# OsciladorLocal.net
KiCad netlist of a schematic drawn in Altium Designer
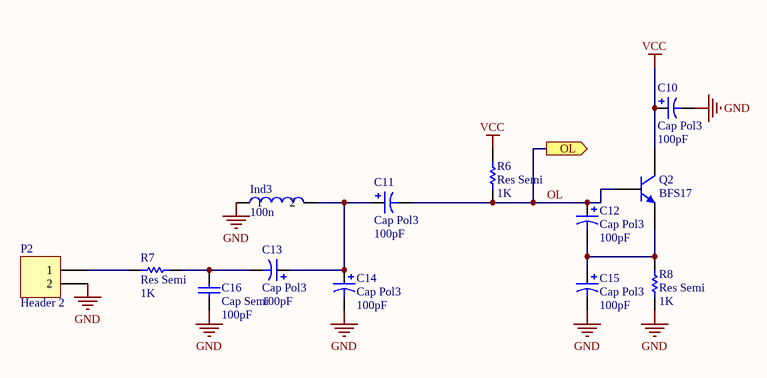
[diagram p0: OsciladorLocal.SchDoc]

(export (version "E")
  (design (tool "Eeschema 10.0.6"))
  (components
    (comp (ref "C10")
      (value "Cap Pol3")
      (footprint "C0805")
      (description "Polarized Capacitor (Surface Mount)")
      (fields (field (name "ALTIUM_VALUE") "100pF") (field (name "PUBLISHER") "Altium Limited"))
      (libsource (lib "Miscellaneous Devices") (part "Cap Pol3"))
    )
    (comp (ref "C11")
      (value "Cap Pol3")
      (footprint "C0805")
      (description "Polarized Capacitor (Surface Mount)")
      (fields (field (name "ALTIUM_VALUE") "100pF") (field (name "PUBLISHER") "Altium Limited"))
      (libsource (lib "Miscellaneous Devices") (part "Cap Pol3"))
    )
    (comp (ref "C12")
      (value "Cap Pol3")
      (footprint "C0805")
      (description "Polarized Capacitor (Surface Mount)")
      (fields (field (name "ALTIUM_VALUE") "100pF") (field (name "PUBLISHER") "Altium Limited"))
      (libsource (lib "Miscellaneous Devices") (part "Cap Pol3"))
    )
    (comp (ref "C13")
      (value "Cap Pol3")
      (footprint "C0805")
      (description "Polarized Capacitor (Surface Mount)")
      (fields (field (name "ALTIUM_VALUE") "100pF") (field (name "PUBLISHER") "Altium Limited"))
      (libsource (lib "Miscellaneous Devices") (part "Cap Pol3"))
    )
    (comp (ref "C14")
      (value "Cap Pol3")
      (footprint "C0805")
      (description "Polarized Capacitor (Surface Mount)")
      (fields (field (name "ALTIUM_VALUE") "100pF") (field (name "PUBLISHER") "Altium Limited"))
      (libsource (lib "Miscellaneous Devices") (part "Cap Pol3"))
    )
    (comp (ref "C15")
      (value "Cap Pol3")
      (footprint "C0805")
      (description "Polarized Capacitor (Surface Mount)")
      (fields (field (name "ALTIUM_VALUE") "100pF") (field (name "PUBLISHER") "Altium Limited"))
      (libsource (lib "Miscellaneous Devices") (part "Cap Pol3"))
    )
    (comp (ref "C16")
      (value "Cap Semi")
      (footprint "C1206")
      (description "Capacitor (Semiconductor SIM Model)")
      (fields (field (name "ALTIUM_VALUE") "100pF") (field (name "PUBLISHER") "Altium Limited"))
      (libsource (lib "Miscellaneous Devices") (part "Cap Semi"))
    )
    (comp (ref "Ind3")
      (value "Ind2")
      (footprint "Ind_3mm")
      (fields (field (name "VALOR") "100n"))
      (libsource (lib "epf") (part "Ind2"))
    )
    (comp (ref "P2")
      (value "Header 2")
      (footprint "HDR1X2")
      (description "Header, 2-Pin")
      (fields (field (name "PUBLISHER") "Altium Limited"))
      (libsource (lib "Miscellaneous Connectors") (part "Header 2"))
    )
    (comp (ref "Q2")
      (value "BFS17")
      (footprint "SOT23_N")
      (description "NPN 1 GHz Wideband Transistor")
      (fields (field (name "PUBLISHER") "Altium Limited"))
      (libsource (lib "Philips Discrete BJT - RF Transistor") (part "BFS17"))
    )
    (comp (ref "R6")
      (value "Res Semi")
      (footprint "2012[0805]")
      (description "Semiconductor Resistor")
      (fields (field (name "ALTIUM_VALUE") "1K") (field (name "PUBLISHER") "Altium Limited"))
      (libsource (lib "Miscellaneous Devices") (part "Res Semi"))
    )
    (comp (ref "R7")
      (value "Res Semi")
      (footprint "2012[0805]")
      (description "Semiconductor Resistor")
      (fields (field (name "ALTIUM_VALUE") "1K") (field (name "PUBLISHER") "Altium Limited"))
      (libsource (lib "Miscellaneous Devices") (part "Res Semi"))
    )
    (comp (ref "R8")
      (value "Res Semi")
      (footprint "2012[0805]")
      (description "Semiconductor Resistor")
      (fields (field (name "ALTIUM_VALUE") "1K") (field (name "PUBLISHER") "Altium Limited"))
      (libsource (lib "Miscellaneous Devices") (part "Res Semi"))
    )
  )
  (nets
    (net (code "1") (name "/OL") (class "Default")
      (node (ref "C11") (pin "2") (pinfunction "2_2") (pintype "passive"))
      (node (ref "C12") (pin "1") (pinfunction "1_1") (pintype "passive"))
      (node (ref "Q2") (pin "1") (pinfunction "B_1") (pintype "passive"))
      (node (ref "R6") (pin "1") (pinfunction "1_1") (pintype "passive"))
    )
    (net (code "2") (name "GND") (class "Default")
      (node (ref "C10") (pin "2") (pinfunction "2_2") (pintype "passive"))
      (node (ref "C14") (pin "2") (pinfunction "2_2") (pintype "passive"))
      (node (ref "C15") (pin "2") (pinfunction "2_2") (pintype "passive"))
      (node (ref "C16") (pin "2") (pinfunction "2_2") (pintype "passive"))
      (node (ref "Ind3") (pin "1") (pinfunction "1_1") (pintype "passive"))
      (node (ref "P2") (pin "2") (pinfunction "2_2") (pintype "passive"))
      (node (ref "R8") (pin "1") (pinfunction "1_1") (pintype "passive"))
    )
    (net (code "3") (name "Net-(C11-Pad1)") (class "Default")
      (node (ref "C11") (pin "1") (pinfunction "1_1") (pintype "passive"))
      (node (ref "C13") (pin "1") (pinfunction "1_1") (pintype "passive"))
      (node (ref "C14") (pin "1") (pinfunction "1_1") (pintype "passive"))
      (node (ref "Ind3") (pin "2") (pinfunction "2_2") (pintype "passive"))
    )
    (net (code "4") (name "Net-(C13-Pad2)") (class "Default")
      (node (ref "C13") (pin "2") (pinfunction "2_2") (pintype "passive"))
      (node (ref "C16") (pin "1") (pinfunction "1_1") (pintype "passive"))
      (node (ref "R7") (pin "2") (pinfunction "2_2") (pintype "passive"))
    )
    (net (code "5") (name "Net-(P2-Pad1)") (class "Default")
      (node (ref "P2") (pin "1") (pinfunction "1_1") (pintype "passive"))
      (node (ref "R7") (pin "1") (pinfunction "1_1") (pintype "passive"))
    )
    (net (code "6") (name "Net-(Q2-E)") (class "Default")
      (node (ref "C12") (pin "2") (pinfunction "2_2") (pintype "passive"))
      (node (ref "C15") (pin "1") (pinfunction "1_1") (pintype "passive"))
      (node (ref "Q2") (pin "2") (pinfunction "E_2") (pintype "passive"))
      (node (ref "R8") (pin "2") (pinfunction "2_2") (pintype "passive"))
    )
    (net (code "7") (name "VCC") (class "Default")
      (node (ref "C10") (pin "1") (pinfunction "1_1") (pintype "passive"))
      (node (ref "Q2") (pin "3") (pinfunction "C_3") (pintype "passive"))
      (node (ref "R6") (pin "2") (pinfunction "2_2") (pintype "passive"))
    )
  )
)
